# low-pass-filter.net
KiCad netlist of a schematic drawn in Altium Designer
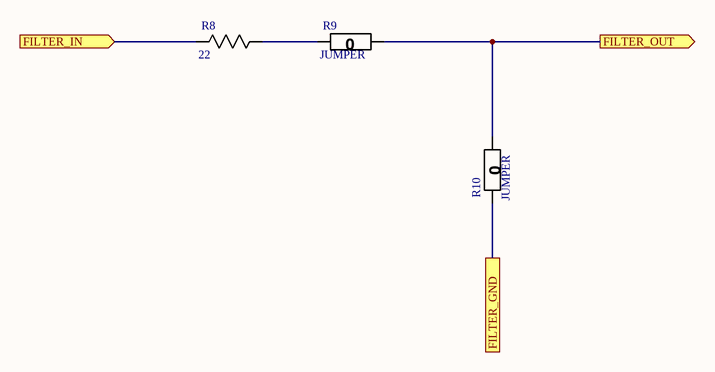
[diagram p0: low-pass-filter.SchDoc]

(export (version "E")
  (design (tool "Eeschema 10.0.6"))
  (components
    (comp (ref "R8")
      (value "22")
      (footprint "0805")
      (description "RES SMD 22 OHM 5% 1/8W 0805")
      (fields (field (name "TOLERANCE") "5%"))
      (libsource (lib "AltiumLibraries") (part "RES 22.0 1/8W"))
    )
    (comp (ref "R9")
      (value "JUMPER")
      (footprint "0805")
      (description "RES SMD 0 OHM JUMPER GENERIC 0805/0603")
      (libsource (lib "AltiumLibraries") (part "RES 0 JUMPER"))
    )
    (comp (ref "R10")
      (value "JUMPER")
      (footprint "0805")
      (description "RES SMD 0 OHM JUMPER GENERIC 0805/0603")
      (libsource (lib "AltiumLibraries") (part "RES 0 JUMPER"))
    )
  )
  (nets
    (net (code "1") (name "/FILTER_GND") (class "Default")
      (node (ref "R10") (pin "2") (pinfunction "R2_2") (pintype "passive"))
    )
    (net (code "2") (name "/FILTER_IN") (class "Default")
      (node (ref "R8") (pin "2") (pinfunction "R2_2") (pintype "passive"))
    )
    (net (code "3") (name "/FILTER_OUT") (class "Default")
      (node (ref "R10") (pin "1") (pinfunction "R1_1") (pintype "passive"))
      (node (ref "R9") (pin "1") (pinfunction "R1_1") (pintype "passive"))
    )
    (net (code "4") (name "Net-(R8-R1)") (class "Default")
      (node (ref "R8") (pin "1") (pinfunction "R1_1") (pintype "passive"))
      (node (ref "R9") (pin "2") (pinfunction "R2_2") (pintype "passive"))
    )
  )
)
